# smartGarden_COM2_Rev01.net
KiCad netlist of a schematic drawn in Altium Designer
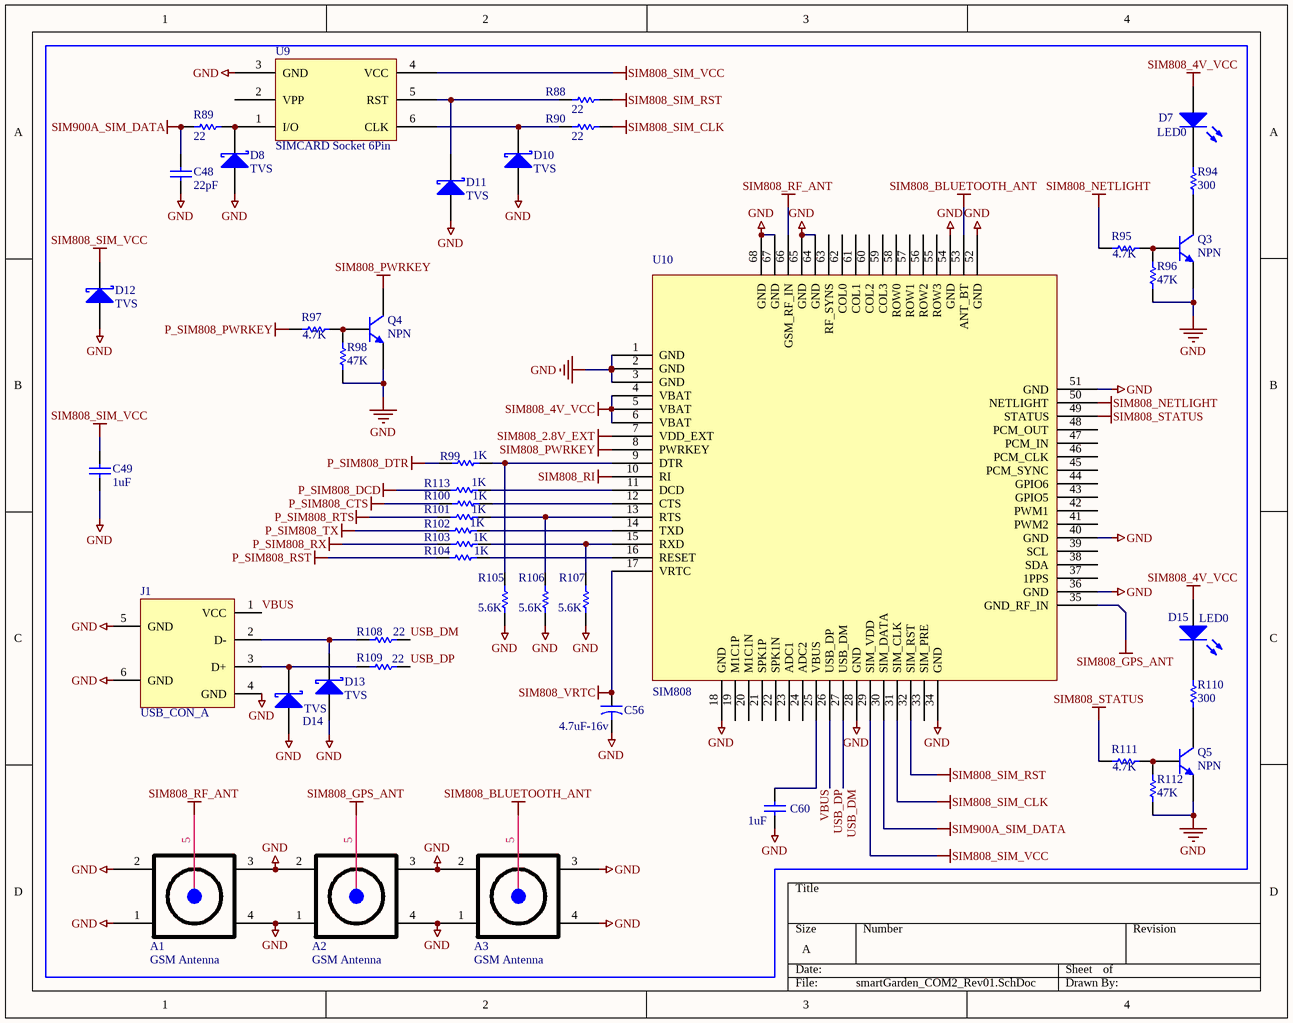
[diagram p0: smartGarden_COM2_Rev01.SchDoc]

(export (version "E")
  (design (tool "Eeschema 10.0.6"))
  (components
    (comp (ref "A1")
      (value "GSM Antenna")
      (footprint "SMA Right Female")
      (libsource (lib "BNB_Altium_LIB_004") (part "SMA KWE-F"))
    )
    (comp (ref "A2")
      (value "GSM Antenna")
      (footprint "SMA Right Female")
      (libsource (lib "BNB_Altium_LIB_004") (part "SMA KWE-F"))
    )
    (comp (ref "A3")
      (value "GSM Antenna")
      (footprint "SMA Right Female")
      (libsource (lib "BNB_Altium_LIB_004") (part "SMA KWE-F"))
    )
    (comp (ref "C48")
      (value "22pF")
      (footprint "0805_smd")
      (description "Capacitor")
      (fields (field (name "PUBLISHER") "Altium Limited"))
      (libsource (lib "Miscellaneous Devices") (part "Cap"))
    )
    (comp (ref "C49")
      (value "1uF")
      (footprint "0805_smd")
      (description "Capacitor")
      (fields (field (name "PUBLISHER") "Altium Limited"))
      (libsource (lib "Miscellaneous Devices") (part "Cap"))
    )
    (comp (ref "C56")
      (value "4.7uF-16v")
      (footprint "CAPR5-4X5")
      (description "Capacitor")
      (fields (field (name "Comment") "Cap2") (field (name "PUBLISHER") "Altium Limited"))
      (libsource (lib "Miscellaneous Devices") (part "Cap2"))
    )
    (comp (ref "C60")
      (value "1uF")
      (footprint "0805_smd")
      (description "Capacitor")
      (fields (field (name "PUBLISHER") "Altium Limited"))
      (libsource (lib "Miscellaneous Devices") (part "Cap"))
    )
    (comp (ref "D7")
      (value "LED0")
      (footprint "0805_LED")
      (description "Typical INFRARED GaAs LED")
      (fields (field (name "PUBLISHER") "Altium Limited"))
      (libsource (lib "Miscellaneous Devices") (part "LED0"))
    )
    (comp (ref "D8")
      (value "TVS")
      (footprint "7227_SMD")
      (description "Schottky Diode")
      (fields (field (name "PUBLISHER") "Altium Limited"))
      (libsource (lib "Miscellaneous Devices") (part "D Schottky"))
    )
    (comp (ref "D10")
      (value "TVS")
      (footprint "7227_SMD")
      (description "Schottky Diode")
      (fields (field (name "PUBLISHER") "Altium Limited"))
      (libsource (lib "Miscellaneous Devices") (part "D Schottky"))
    )
    (comp (ref "D11")
      (value "TVS")
      (footprint "7227_SMD")
      (description "Schottky Diode")
      (fields (field (name "PUBLISHER") "Altium Limited"))
      (libsource (lib "Miscellaneous Devices") (part "D Schottky"))
    )
    (comp (ref "D12")
      (value "TVS")
      (footprint "7227_SMD")
      (description "Schottky Diode")
      (fields (field (name "PUBLISHER") "Altium Limited"))
      (libsource (lib "Miscellaneous Devices") (part "D Schottky"))
    )
    (comp (ref "D13")
      (value "TVS")
      (footprint "7227_SMD")
      (description "Schottky Diode")
      (fields (field (name "PUBLISHER") "Altium Limited"))
      (libsource (lib "Miscellaneous Devices") (part "D Schottky"))
    )
    (comp (ref "D14")
      (value "TVS")
      (footprint "7227_SMD")
      (description "Schottky Diode")
      (fields (field (name "PUBLISHER") "Altium Limited"))
      (libsource (lib "Miscellaneous Devices") (part "D Schottky"))
    )
    (comp (ref "D15")
      (value "LED0")
      (footprint "0805_LED")
      (description "Typical INFRARED GaAs LED")
      (fields (field (name "PUBLISHER") "Altium Limited"))
      (libsource (lib "Miscellaneous Devices") (part "LED0"))
    )
    (comp (ref "J1")
      (value "USB_CON_A")
      (footprint "USB_CON_A")
      (libsource (lib "MYLib524") (part "USB_CON_A"))
    )
    (comp (ref "Q3")
      (value "NPN")
      (footprint "TO-226-AA")
      (description "NPN Bipolar Transistor")
      (fields (field (name "PUBLISHER") "Altium Limited"))
      (libsource (lib "Miscellaneous Devices") (part "NPN"))
    )
    (comp (ref "Q4")
      (value "NPN")
      (footprint "TO-226-AA")
      (description "NPN Bipolar Transistor")
      (fields (field (name "PUBLISHER") "Altium Limited"))
      (libsource (lib "Miscellaneous Devices") (part "NPN"))
    )
    (comp (ref "Q5")
      (value "NPN")
      (footprint "TO-226-AA")
      (description "NPN Bipolar Transistor")
      (fields (field (name "PUBLISHER") "Altium Limited"))
      (libsource (lib "Miscellaneous Devices") (part "NPN"))
    )
    (comp (ref "R88")
      (value "22")
      (footprint "0805_SMD")
      (description "Resistor")
      (fields (field (name "PUBLISHER") "Altium Limited"))
      (libsource (lib "Miscellaneous Devices") (part "Res1"))
    )
    (comp (ref "R89")
      (value "22")
      (footprint "1206_SMD")
      (description "Resistor")
      (fields (field (name "PUBLISHER") "Altium Limited"))
      (libsource (lib "Miscellaneous Devices") (part "Res1"))
    )
    (comp (ref "R90")
      (value "22")
      (footprint "0805_SMD")
      (description "Resistor")
      (fields (field (name "PUBLISHER") "Altium Limited"))
      (libsource (lib "Miscellaneous Devices") (part "Res1"))
    )
    (comp (ref "R94")
      (value "300")
      (footprint "0805_SMD")
      (description "Resistor")
      (fields (field (name "PUBLISHER") "Altium Limited"))
      (libsource (lib "Miscellaneous Devices") (part "Res1"))
    )
    (comp (ref "R95")
      (value "4.7K")
      (footprint "0805_SMD")
      (description "Resistor")
      (fields (field (name "PUBLISHER") "Altium Limited"))
      (libsource (lib "Miscellaneous Devices") (part "Res1"))
    )
    (comp (ref "R96")
      (value "47K")
      (footprint "0805_SMD")
      (description "Resistor")
      (fields (field (name "PUBLISHER") "Altium Limited"))
      (libsource (lib "Miscellaneous Devices") (part "Res1"))
    )
    (comp (ref "R97")
      (value "4.7K")
      (footprint "0805_SMD")
      (description "Resistor")
      (fields (field (name "PUBLISHER") "Altium Limited"))
      (libsource (lib "Miscellaneous Devices") (part "Res1"))
    )
    (comp (ref "R98")
      (value "47K")
      (footprint "0805_SMD")
      (description "Resistor")
      (fields (field (name "PUBLISHER") "Altium Limited"))
      (libsource (lib "Miscellaneous Devices") (part "Res1"))
    )
    (comp (ref "R99")
      (value "1K")
      (footprint "1206_SMD")
      (description "Resistor")
      (fields (field (name "PUBLISHER") "Altium Limited"))
      (libsource (lib "Miscellaneous Devices") (part "Res1"))
    )
    (comp (ref "R100")
      (value "1K")
      (footprint "1206_SMD")
      (description "Resistor")
      (fields (field (name "PUBLISHER") "Altium Limited"))
      (libsource (lib "Miscellaneous Devices") (part "Res1"))
    )
    (comp (ref "R101")
      (value "1K")
      (footprint "1206_SMD")
      (description "Resistor")
      (fields (field (name "PUBLISHER") "Altium Limited"))
      (libsource (lib "Miscellaneous Devices") (part "Res1"))
    )
    (comp (ref "R102")
      (value "1K")
      (footprint "1206_SMD")
      (description "Resistor")
      (fields (field (name "PUBLISHER") "Altium Limited"))
      (libsource (lib "Miscellaneous Devices") (part "Res1"))
    )
    (comp (ref "R103")
      (value "1K")
      (footprint "1206_SMD")
      (description "Resistor")
      (fields (field (name "PUBLISHER") "Altium Limited"))
      (libsource (lib "Miscellaneous Devices") (part "Res1"))
    )
    (comp (ref "R104")
      (value "1K")
      (footprint "1206_SMD")
      (description "Resistor")
      (fields (field (name "PUBLISHER") "Altium Limited"))
      (libsource (lib "Miscellaneous Devices") (part "Res1"))
    )
    (comp (ref "R105")
      (value "5.6K")
      (footprint "1206_SMD")
      (description "Resistor")
      (fields (field (name "PUBLISHER") "Altium Limited"))
      (libsource (lib "Miscellaneous Devices") (part "Res1"))
    )
    (comp (ref "R106")
      (value "5.6K")
      (footprint "1206_SMD")
      (description "Resistor")
      (fields (field (name "PUBLISHER") "Altium Limited"))
      (libsource (lib "Miscellaneous Devices") (part "Res1"))
    )
    (comp (ref "R107")
      (value "5.6K")
      (footprint "1206_SMD")
      (description "Resistor")
      (fields (field (name "PUBLISHER") "Altium Limited"))
      (libsource (lib "Miscellaneous Devices") (part "Res1"))
    )
    (comp (ref "R108")
      (value "22")
      (footprint "1206_SMD")
      (description "Resistor")
      (fields (field (name "PUBLISHER") "Altium Limited"))
      (libsource (lib "Miscellaneous Devices") (part "Res1"))
    )
    (comp (ref "R109")
      (value "22")
      (footprint "1206_SMD")
      (description "Resistor")
      (fields (field (name "PUBLISHER") "Altium Limited"))
      (libsource (lib "Miscellaneous Devices") (part "Res1"))
    )
    (comp (ref "R110")
      (value "300")
      (footprint "0805_SMD")
      (description "Resistor")
      (fields (field (name "PUBLISHER") "Altium Limited"))
      (libsource (lib "Miscellaneous Devices") (part "Res1"))
    )
    (comp (ref "R111")
      (value "4.7K")
      (footprint "0805_SMD")
      (description "Resistor")
      (fields (field (name "PUBLISHER") "Altium Limited"))
      (libsource (lib "Miscellaneous Devices") (part "Res1"))
    )
    (comp (ref "R112")
      (value "47K")
      (footprint "0805_SMD")
      (description "Resistor")
      (fields (field (name "PUBLISHER") "Altium Limited"))
      (libsource (lib "Miscellaneous Devices") (part "Res1"))
    )
    (comp (ref "R113")
      (value "1K")
      (footprint "1206_SMD")
      (description "Resistor")
      (fields (field (name "PUBLISHER") "Altium Limited"))
      (libsource (lib "Miscellaneous Devices") (part "Res1"))
    )
    (comp (ref "U9")
      (value "SIMCARD Socket 6Pin")
      (footprint "6PIN _SIMCARD")
      (libsource (lib "BNB_Altium_LIB_004") (part "SIM_SOCKET_6PIN"))
    )
    (comp (ref "U10") (value "SIM808") (libsource (lib "MYLib524") (part "SIM 808 GSM/GPRS/GPS")))
  )
  (nets
    (net (code "1") (name "/USB_DM") (class "Default")
      (node (ref "R108") (pin "2") (pinfunction "2_2") (pintype "passive"))
      (node (ref "U10") (pin "27") (pinfunction "USB_DM_27") (pintype "passive"))
    )
    (net (code "2") (name "/USB_DP") (class "Default")
      (node (ref "R109") (pin "2") (pinfunction "2_2") (pintype "passive"))
      (node (ref "U10") (pin "26") (pinfunction "USB_DP_26") (pintype "passive"))
    )
    (net (code "3") (name "/VBUS") (class "Default")
      (node (ref "C60") (pin "2") (pinfunction "2_2") (pintype "passive"))
      (node (ref "J1") (pin "1") (pinfunction "VCC_1") (pintype "passive"))
      (node (ref "U10") (pin "25") (pinfunction "VBUS_25") (pintype "passive"))
    )
    (net (code "4") (name "GND") (class "Default")
      (node (ref "A1") (pin "1") (pintype "passive"))
      (node (ref "A1") (pin "2") (pintype "passive"))
      (node (ref "A1") (pin "3") (pintype "passive"))
      (node (ref "A1") (pin "4") (pintype "passive"))
      (node (ref "A2") (pin "1") (pintype "passive"))
      (node (ref "A2") (pin "2") (pintype "passive"))
      (node (ref "A2") (pin "3") (pintype "passive"))
      (node (ref "A2") (pin "4") (pintype "passive"))
      (node (ref "A3") (pin "1") (pintype "passive"))
      (node (ref "A3") (pin "2") (pintype "passive"))
      (node (ref "A3") (pin "3") (pintype "passive"))
      (node (ref "A3") (pin "4") (pintype "passive"))
      (node (ref "C48") (pin "1") (pinfunction "1_1") (pintype "passive"))
      (node (ref "C49") (pin "1") (pinfunction "1_1") (pintype "passive"))
      (node (ref "C56") (pin "2") (pinfunction "2_2") (pintype "passive"))
      (node (ref "C60") (pin "1") (pinfunction "1_1") (pintype "passive"))
      (node (ref "D10") (pin "A") (pinfunction "A_A") (pintype "passive"))
      (node (ref "D11") (pin "A") (pinfunction "A_A") (pintype "passive"))
      (node (ref "D12") (pin "A") (pinfunction "A_A") (pintype "passive"))
      (node (ref "D13") (pin "A") (pinfunction "A_A") (pintype "passive"))
      (node (ref "D14") (pin "A") (pinfunction "A_A") (pintype "passive"))
      (node (ref "D8") (pin "A") (pinfunction "A_A") (pintype "passive"))
      (node (ref "J1") (pin "4") (pinfunction "GND_4") (pintype "passive"))
      (node (ref "J1") (pin "5") (pinfunction "GND_5") (pintype "passive"))
      (node (ref "J1") (pin "6") (pinfunction "GND_6") (pintype "passive"))
      (node (ref "Q3") (pin "3") (pinfunction "E_3") (pintype "passive"))
      (node (ref "Q4") (pin "3") (pinfunction "E_3") (pintype "passive"))
      (node (ref "Q5") (pin "3") (pinfunction "E_3") (pintype "passive"))
      (node (ref "R105") (pin "2") (pinfunction "2_2") (pintype "passive"))
      (node (ref "R106") (pin "2") (pinfunction "2_2") (pintype "passive"))
      (node (ref "R107") (pin "2") (pinfunction "2_2") (pintype "passive"))
      (node (ref "R112") (pin "1") (pinfunction "1_1") (pintype "passive"))
      (node (ref "R96") (pin "1") (pinfunction "1_1") (pintype "passive"))
      (node (ref "R98") (pin "1") (pinfunction "1_1") (pintype "passive"))
      (node (ref "U10") (pin "1") (pinfunction "GND_1") (pintype "passive"))
      (node (ref "U10") (pin "18") (pinfunction "GND_18") (pintype "passive"))
      (node (ref "U10") (pin "2") (pinfunction "GND_2") (pintype "passive"))
      (node (ref "U10") (pin "28") (pinfunction "GND_28") (pintype "passive"))
      (node (ref "U10") (pin "3") (pinfunction "GND_3") (pintype "passive"))
      (node (ref "U10") (pin "34") (pinfunction "GND_34") (pintype "passive"))
      (node (ref "U10") (pin "36") (pinfunction "GND_36") (pintype "passive"))
      (node (ref "U10") (pin "40") (pinfunction "GND_40") (pintype "passive"))
      (node (ref "U10") (pin "51") (pinfunction "GND_51") (pintype "passive"))
      (node (ref "U10") (pin "52") (pinfunction "GND_52") (pintype "passive"))
      (node (ref "U10") (pin "54") (pinfunction "GND_54") (pintype "passive"))
      (node (ref "U10") (pin "64") (pinfunction "GND_64") (pintype "passive"))
      (node (ref "U10") (pin "65") (pinfunction "GND_65") (pintype "passive"))
      (node (ref "U10") (pin "67") (pinfunction "GND_67") (pintype "passive"))
      (node (ref "U10") (pin "68") (pinfunction "GND_68") (pintype "passive"))
      (node (ref "U9") (pin "3") (pinfunction "GND_3") (pintype "passive"))
    )
    (net (code "5") (name "Net-(D7-K)") (class "Default")
      (node (ref "D7") (pin "2") (pinfunction "K_2") (pintype "passive"))
      (node (ref "R94") (pin "2") (pinfunction "2_2") (pintype "passive"))
    )
    (net (code "6") (name "Net-(D15-K)") (class "Default")
      (node (ref "D15") (pin "2") (pinfunction "K_2") (pintype "passive"))
      (node (ref "R110") (pin "2") (pinfunction "2_2") (pintype "passive"))
    )
    (net (code "7") (name "Net-(J1-D+)") (class "Default")
      (node (ref "D14") (pin "K") (pinfunction "K_K") (pintype "passive"))
      (node (ref "J1") (pin "3") (pinfunction "D+_3") (pintype "passive"))
      (node (ref "R109") (pin "1") (pinfunction "1_1") (pintype "passive"))
    )
    (net (code "8") (name "Net-(J1-D-)") (class "Default")
      (node (ref "D13") (pin "K") (pinfunction "K_K") (pintype "passive"))
      (node (ref "J1") (pin "2") (pinfunction "D-_2") (pintype "passive"))
      (node (ref "R108") (pin "1") (pinfunction "1_1") (pintype "passive"))
    )
    (net (code "9") (name "Net-(Q3-B)") (class "Default")
      (node (ref "Q3") (pin "2") (pinfunction "B_2") (pintype "passive"))
      (node (ref "R95") (pin "2") (pinfunction "2_2") (pintype "passive"))
      (node (ref "R96") (pin "2") (pinfunction "2_2") (pintype "passive"))
    )
    (net (code "10") (name "Net-(Q3-C)") (class "Default")
      (node (ref "Q3") (pin "1") (pinfunction "C_1") (pintype "passive"))
      (node (ref "R94") (pin "1") (pinfunction "1_1") (pintype "passive"))
    )
    (net (code "11") (name "Net-(Q4-B)") (class "Default")
      (node (ref "Q4") (pin "2") (pinfunction "B_2") (pintype "passive"))
      (node (ref "R97") (pin "2") (pinfunction "2_2") (pintype "passive"))
      (node (ref "R98") (pin "2") (pinfunction "2_2") (pintype "passive"))
    )
    (net (code "12") (name "Net-(Q5-B)") (class "Default")
      (node (ref "Q5") (pin "2") (pinfunction "B_2") (pintype "passive"))
      (node (ref "R111") (pin "2") (pinfunction "2_2") (pintype "passive"))
      (node (ref "R112") (pin "2") (pinfunction "2_2") (pintype "passive"))
    )
    (net (code "13") (name "Net-(Q5-C)") (class "Default")
      (node (ref "Q5") (pin "1") (pinfunction "C_1") (pintype "passive"))
      (node (ref "R110") (pin "1") (pinfunction "1_1") (pintype "passive"))
    )
    (net (code "14") (name "Net-(U9-CLK)") (class "Default")
      (node (ref "D10") (pin "K") (pinfunction "K_K") (pintype "passive"))
      (node (ref "R90") (pin "1") (pinfunction "1_1") (pintype "passive"))
      (node (ref "U9") (pin "6") (pinfunction "CLK_6") (pintype "passive"))
    )
    (net (code "15") (name "Net-(U9-I{slash}O)") (class "Default")
      (node (ref "D8") (pin "K") (pinfunction "K_K") (pintype "passive"))
      (node (ref "R89") (pin "1") (pinfunction "1_1") (pintype "passive"))
      (node (ref "U9") (pin "1") (pinfunction "I/O_1") (pintype "passive"))
    )
    (net (code "16") (name "Net-(U9-RST)") (class "Default")
      (node (ref "D11") (pin "K") (pinfunction "K_K") (pintype "passive"))
      (node (ref "R88") (pin "1") (pinfunction "1_1") (pintype "passive"))
      (node (ref "U9") (pin "5") (pinfunction "RST_5") (pintype "passive"))
    )
    (net (code "17") (name "Net-(U10-CTS)") (class "Default")
      (node (ref "R100") (pin "1") (pinfunction "1_1") (pintype "passive"))
      (node (ref "U10") (pin "12") (pinfunction "CTS_12") (pintype "passive"))
    )
    (net (code "18") (name "Net-(U10-DCD)") (class "Default")
      (node (ref "R113") (pin "1") (pinfunction "1_1") (pintype "passive"))
      (node (ref "U10") (pin "11") (pinfunction "DCD_11") (pintype "passive"))
    )
    (net (code "19") (name "Net-(U10-DTR)") (class "Default")
      (node (ref "R105") (pin "1") (pinfunction "1_1") (pintype "passive"))
      (node (ref "R99") (pin "1") (pinfunction "1_1") (pintype "passive"))
      (node (ref "U10") (pin "9") (pinfunction "DTR_9") (pintype "passive"))
    )
    (net (code "20") (name "Net-(U10-RESET)") (class "Default")
      (node (ref "R104") (pin "1") (pinfunction "1_1") (pintype "passive"))
      (node (ref "U10") (pin "16") (pinfunction "RESET_16") (pintype "passive"))
    )
    (net (code "21") (name "Net-(U10-RTS)") (class "Default")
      (node (ref "R101") (pin "1") (pinfunction "1_1") (pintype "passive"))
      (node (ref "R106") (pin "1") (pinfunction "1_1") (pintype "passive"))
      (node (ref "U10") (pin "13") (pinfunction "RTS_13") (pintype "passive"))
    )
    (net (code "22") (name "Net-(U10-RXD)") (class "Default")
      (node (ref "R103") (pin "1") (pinfunction "1_1") (pintype "passive"))
      (node (ref "R107") (pin "1") (pinfunction "1_1") (pintype "passive"))
      (node (ref "U10") (pin "15") (pinfunction "RXD_15") (pintype "passive"))
    )
    (net (code "23") (name "Net-(U10-TXD)") (class "Default")
      (node (ref "R102") (pin "1") (pinfunction "1_1") (pintype "passive"))
      (node (ref "U10") (pin "14") (pinfunction "TXD_14") (pintype "passive"))
    )
    (net (code "24") (name "P_SIM808_CTS") (class "Default")
      (node (ref "R100") (pin "2") (pinfunction "2_2") (pintype "passive"))
    )
    (net (code "25") (name "P_SIM808_DCD") (class "Default")
      (node (ref "R113") (pin "2") (pinfunction "2_2") (pintype "passive"))
    )
    (net (code "26") (name "P_SIM808_DTR") (class "Default")
      (node (ref "R99") (pin "2") (pinfunction "2_2") (pintype "passive"))
    )
    (net (code "27") (name "P_SIM808_PWRKEY") (class "Default")
      (node (ref "R97") (pin "1") (pinfunction "1_1") (pintype "passive"))
    )
    (net (code "28") (name "P_SIM808_RST") (class "Default")
      (node (ref "R104") (pin "2") (pinfunction "2_2") (pintype "passive"))
    )
    (net (code "29") (name "P_SIM808_RTS") (class "Default")
      (node (ref "R101") (pin "2") (pinfunction "2_2") (pintype "passive"))
    )
    (net (code "30") (name "P_SIM808_RX") (class "Default")
      (node (ref "R103") (pin "2") (pinfunction "2_2") (pintype "passive"))
    )
    (net (code "31") (name "P_SIM808_TX") (class "Default")
      (node (ref "R102") (pin "2") (pinfunction "2_2") (pintype "passive"))
    )
    (net (code "32") (name "SIM808_2.8V_EXT") (class "Default")
      (node (ref "U10") (pin "7") (pinfunction "VDD_EXT_7") (pintype "passive"))
    )
    (net (code "33") (name "SIM808_4V_VCC") (class "Default")
      (node (ref "D15") (pin "1") (pinfunction "A_1") (pintype "passive"))
      (node (ref "D7") (pin "1") (pinfunction "A_1") (pintype "passive"))
      (node (ref "U10") (pin "4") (pinfunction "VBAT_4") (pintype "passive"))
      (node (ref "U10") (pin "5") (pinfunction "VBAT_5") (pintype "passive"))
      (node (ref "U10") (pin "6") (pinfunction "VBAT_6") (pintype "passive"))
    )
    (net (code "34") (name "SIM808_BLUETOOTH_ANT") (class "Default")
      (node (ref "A3") (pin "5") (pintype "passive"))
      (node (ref "U10") (pin "53") (pinfunction "ANT_BT_53") (pintype "passive"))
    )
    (net (code "35") (name "SIM808_GPS_ANT") (class "Default")
      (node (ref "A2") (pin "5") (pintype "passive"))
      (node (ref "U10") (pin "35") (pinfunction "GND_RF_IN_35") (pintype "passive"))
    )
    (net (code "36") (name "SIM808_NETLIGHT") (class "Default")
      (node (ref "R95") (pin "1") (pinfunction "1_1") (pintype "passive"))
      (node (ref "U10") (pin "50") (pinfunction "NETLIGHT_50") (pintype "passive"))
    )
    (net (code "37") (name "SIM808_PWRKEY") (class "Default")
      (node (ref "Q4") (pin "1") (pinfunction "C_1") (pintype "passive"))
      (node (ref "U10") (pin "8") (pinfunction "PWRKEY_8") (pintype "passive"))
    )
    (net (code "38") (name "SIM808_RF_ANT") (class "Default")
      (node (ref "A1") (pin "5") (pintype "passive"))
      (node (ref "U10") (pin "66") (pinfunction "GSM_RF_IN_66") (pintype "passive"))
    )
    (net (code "39") (name "SIM808_RI") (class "Default")
      (node (ref "U10") (pin "10") (pinfunction "RI_10") (pintype "passive"))
    )
    (net (code "40") (name "SIM808_SIM_CLK") (class "Default")
      (node (ref "R90") (pin "2") (pinfunction "2_2") (pintype "passive"))
      (node (ref "U10") (pin "31") (pinfunction "SIM_CLK_31") (pintype "passive"))
    )
    (net (code "41") (name "SIM808_SIM_RST") (class "Default")
      (node (ref "R88") (pin "2") (pinfunction "2_2") (pintype "passive"))
      (node (ref "U10") (pin "32") (pinfunction "SIM_RST_32") (pintype "passive"))
    )
    (net (code "42") (name "SIM808_SIM_VCC") (class "Default")
      (node (ref "C49") (pin "2") (pinfunction "2_2") (pintype "passive"))
      (node (ref "D12") (pin "K") (pinfunction "K_K") (pintype "passive"))
      (node (ref "U10") (pin "29") (pinfunction "SIM_VDD_29") (pintype "passive"))
      (node (ref "U9") (pin "4") (pinfunction "VCC_4") (pintype "passive"))
    )
    (net (code "43") (name "SIM808_STATUS") (class "Default")
      (node (ref "R111") (pin "1") (pinfunction "1_1") (pintype "passive"))
      (node (ref "U10") (pin "49") (pinfunction "STATUS_49") (pintype "passive"))
    )
    (net (code "44") (name "SIM808_VRTC") (class "Default")
      (node (ref "C56") (pin "1") (pinfunction "1_1") (pintype "passive"))
      (node (ref "U10") (pin "17") (pinfunction "VRTC_17") (pintype "passive"))
    )
    (net (code "45") (name "SIM900A_SIM_DATA") (class "Default")
      (node (ref "C48") (pin "2") (pinfunction "2_2") (pintype "passive"))
      (node (ref "R89") (pin "2") (pinfunction "2_2") (pintype "passive"))
      (node (ref "U10") (pin "30") (pinfunction "SIM_DATA_30") (pintype "passive"))
    )
    (net (code "46") (name "unconnected-(U9-VPP-Pad2)") (class "Default")
      (node (ref "U9") (pin "2") (pinfunction "VPP_2") (pintype "passive"))
    )
    (net (code "47") (name "unconnected-(U10-1PPS-Pad37)") (class "Default")
      (node (ref "U10") (pin "37") (pinfunction "1PPS_37") (pintype "passive"))
    )
    (net (code "48") (name "unconnected-(U10-ADC1-Pad23)") (class "Default")
      (node (ref "U10") (pin "23") (pinfunction "ADC1_23") (pintype "passive"))
    )
    (net (code "49") (name "unconnected-(U10-ADC2-Pad24)") (class "Default")
      (node (ref "U10") (pin "24") (pinfunction "ADC2_24") (pintype "passive"))
    )
    (net (code "50") (name "unconnected-(U10-COL0-Pad62)") (class "Default")
      (node (ref "U10") (pin "62") (pinfunction "COL0_62") (pintype "passive"))
    )
    (net (code "51") (name "unconnected-(U10-COL1-Pad61)") (class "Default")
      (node (ref "U10") (pin "61") (pinfunction "COL1_61") (pintype "passive"))
    )
    (net (code "52") (name "unconnected-(U10-COL2-Pad60)") (class "Default")
      (node (ref "U10") (pin "60") (pinfunction "COL2_60") (pintype "passive"))
    )
    (net (code "53") (name "unconnected-(U10-COL3-Pad59)") (class "Default")
      (node (ref "U10") (pin "59") (pinfunction "COL3_59") (pintype "passive"))
    )
    (net (code "54") (name "unconnected-(U10-GPIO5-Pad43)") (class "Default")
      (node (ref "U10") (pin "43") (pinfunction "GPIO5_43") (pintype "passive"))
    )
    (net (code "55") (name "unconnected-(U10-GPIO6-Pad44)") (class "Default")
      (node (ref "U10") (pin "44") (pinfunction "GPIO6_44") (pintype "passive"))
    )
    (net (code "56") (name "unconnected-(U10-M1C1N-Pad20)") (class "Default")
      (node (ref "U10") (pin "20") (pinfunction "M1C1N_20") (pintype "passive"))
    )
    (net (code "57") (name "unconnected-(U10-M1C1P-Pad19)") (class "Default")
      (node (ref "U10") (pin "19") (pinfunction "M1C1P_19") (pintype "passive"))
    )
    (net (code "58") (name "unconnected-(U10-PCM_CLK-Pad46)") (class "Default")
      (node (ref "U10") (pin "46") (pinfunction "PCM_CLK_46") (pintype "passive"))
    )
    (net (code "59") (name "unconnected-(U10-PCM_IN-Pad47)") (class "Default")
      (node (ref "U10") (pin "47") (pinfunction "PCM_IN_47") (pintype "passive"))
    )
    (net (code "60") (name "unconnected-(U10-PCM_OUT-Pad48)") (class "Default")
      (node (ref "U10") (pin "48") (pinfunction "PCM_OUT_48") (pintype "passive"))
    )
    (net (code "61") (name "unconnected-(U10-PCM_SYNC-Pad45)") (class "Default")
      (node (ref "U10") (pin "45") (pinfunction "PCM_SYNC_45") (pintype "passive"))
    )
    (net (code "62") (name "unconnected-(U10-PWM1-Pad42)") (class "Default")
      (node (ref "U10") (pin "42") (pinfunction "PWM1_42") (pintype "passive"))
    )
    (net (code "63") (name "unconnected-(U10-PWM2-Pad41)") (class "Default")
      (node (ref "U10") (pin "41") (pinfunction "PWM2_41") (pintype "passive"))
    )
    (net (code "64") (name "unconnected-(U10-RF_SYNS-Pad63)") (class "Default")
      (node (ref "U10") (pin "63") (pinfunction "RF_SYNS_63") (pintype "passive"))
    )
    (net (code "65") (name "unconnected-(U10-ROW0-Pad58)") (class "Default")
      (node (ref "U10") (pin "58") (pinfunction "ROW0_58") (pintype "passive"))
    )
    (net (code "66") (name "unconnected-(U10-ROW1-Pad57)") (class "Default")
      (node (ref "U10") (pin "57") (pinfunction "ROW1_57") (pintype "passive"))
    )
    (net (code "67") (name "unconnected-(U10-ROW2-Pad56)") (class "Default")
      (node (ref "U10") (pin "56") (pinfunction "ROW2_56") (pintype "passive"))
    )
    (net (code "68") (name "unconnected-(U10-ROW3-Pad55)") (class "Default")
      (node (ref "U10") (pin "55") (pinfunction "ROW3_55") (pintype "passive"))
    )
    (net (code "69") (name "unconnected-(U10-SCL-Pad39)") (class "Default")
      (node (ref "U10") (pin "39") (pinfunction "SCL_39") (pintype "passive"))
    )
    (net (code "70") (name "unconnected-(U10-SDA-Pad38)") (class "Default")
      (node (ref "U10") (pin "38") (pinfunction "SDA_38") (pintype "passive"))
    )
    (net (code "71") (name "unconnected-(U10-SIM_PRE-Pad33)") (class "Default")
      (node (ref "U10") (pin "33") (pinfunction "SIM_PRE_33") (pintype "passive"))
    )
    (net (code "72") (name "unconnected-(U10-SPK1N-Pad22)") (class "Default")
      (node (ref "U10") (pin "22") (pinfunction "SPK1N_22") (pintype "passive"))
    )
    (net (code "73") (name "unconnected-(U10-SPK1P-Pad21)") (class "Default")
      (node (ref "U10") (pin "21") (pinfunction "SPK1P_21") (pintype "passive"))
    )
  )
)
